# CAN.net
KiCad netlist of a schematic drawn in Altium Designer
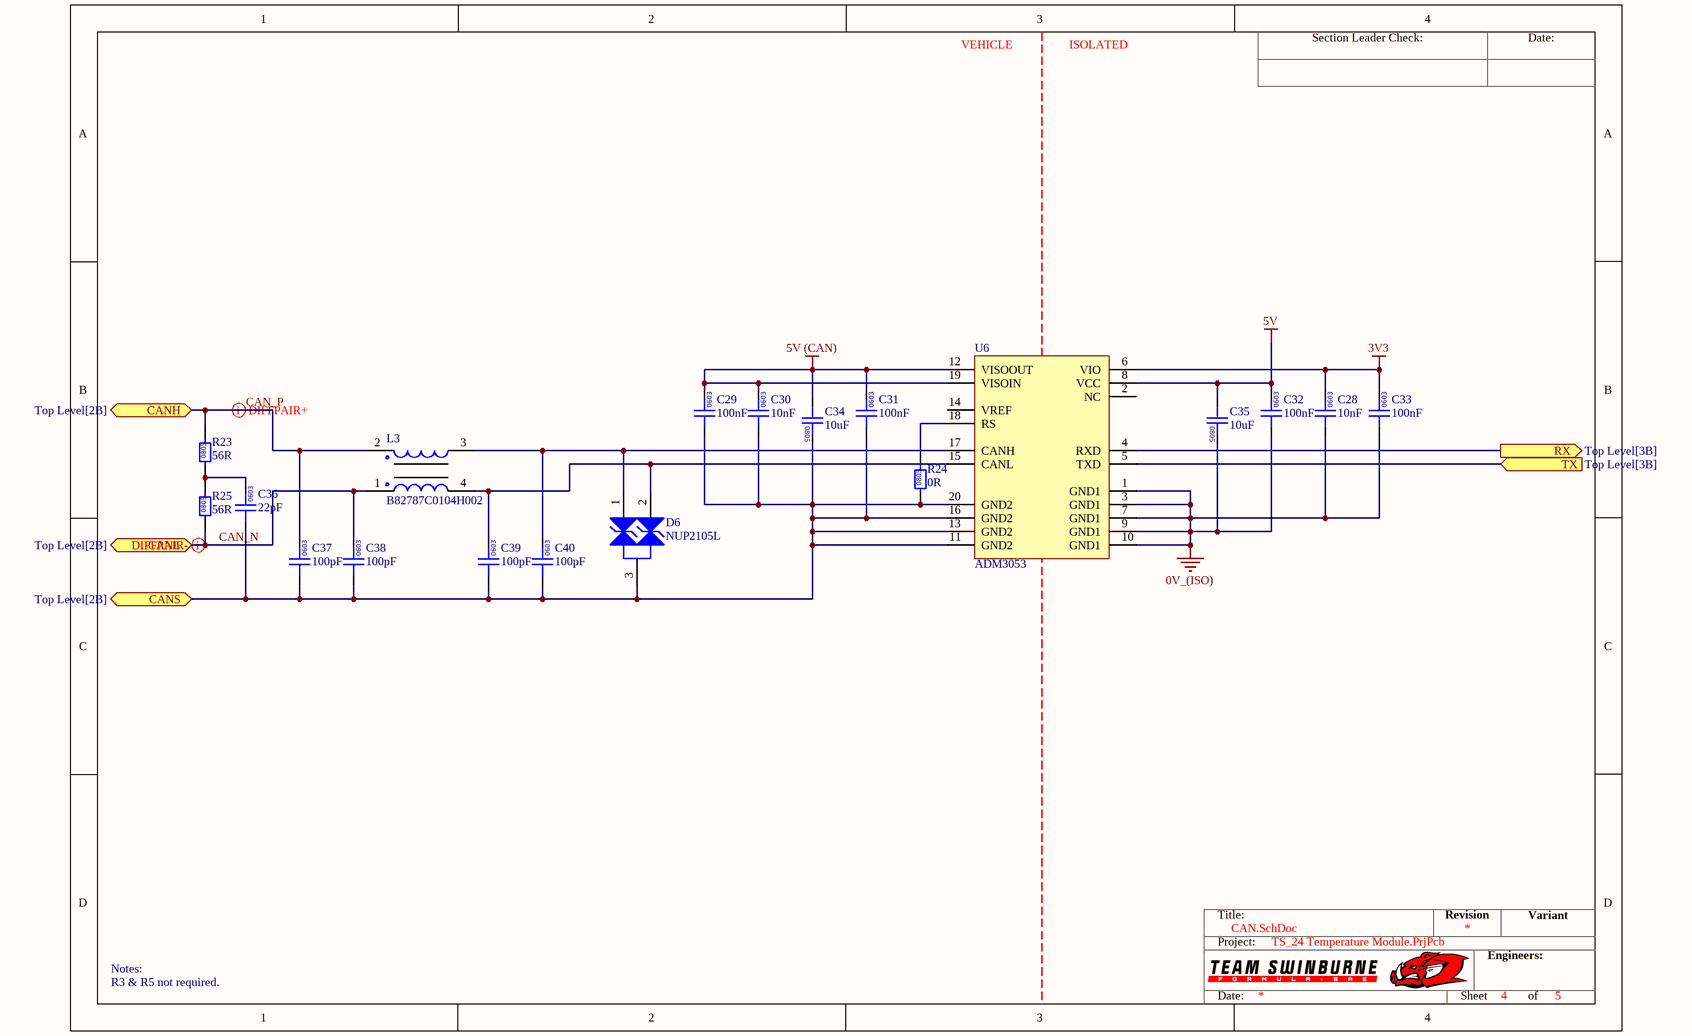
[diagram p0: CAN.SchDoc]

(export (version "E")
  (design (tool "Eeschema 10.0.6"))
  (components
    (comp (ref "C28")
      (value "10nF")
      (footprint "0603")
      (fields
        (field (name "PART NUMBER") "GCM188L81H103KA03D")
        (field (name "MANUFACTURER") "muRata")
        (field (name "TOLERANCE") "±10%")
      )
      (libsource (lib "ts_standard_library") (part "Capacitor 0603"))
    )
    (comp (ref "C29")
      (value "100nF")
      (footprint "0603")
      (fields
        (field (name "PART NUMBER") "GCM188L81H104KA57D")
        (field (name "MANUFACTURER") "muRata")
        (field (name "TOLERANCE") "±10%")
      )
      (libsource (lib "ts_standard_library") (part "Capacitor 0603"))
    )
    (comp (ref "C30")
      (value "10nF")
      (footprint "0603")
      (fields
        (field (name "PART NUMBER") "GCM188L81H103KA03D")
        (field (name "MANUFACTURER") "muRata")
        (field (name "TOLERANCE") "±10%")
      )
      (libsource (lib "ts_standard_library") (part "Capacitor 0603"))
    )
    (comp (ref "C31")
      (value "100nF")
      (footprint "0603")
      (fields
        (field (name "PART NUMBER") "GCM188L81H104KA57D")
        (field (name "MANUFACTURER") "muRata")
        (field (name "TOLERANCE") "±10%")
      )
      (libsource (lib "ts_standard_library") (part "Capacitor 0603"))
    )
    (comp (ref "C32")
      (value "100nF")
      (footprint "0603")
      (fields
        (field (name "PART NUMBER") "GCM188L81H104KA57D")
        (field (name "MANUFACTURER") "muRata")
        (field (name "TOLERANCE") "±10%")
      )
      (libsource (lib "ts_standard_library") (part "Capacitor 0603"))
    )
    (comp (ref "C33")
      (value "100nF")
      (footprint "0603")
      (fields
        (field (name "PART NUMBER") "GCM188L81H104KA57D")
        (field (name "MANUFACTURER") "muRata")
        (field (name "TOLERANCE") "±10%")
      )
      (libsource (lib "ts_standard_library") (part "Capacitor 0603"))
    )
    (comp (ref "C34")
      (value "10uF")
      (footprint "0805")
      (fields
        (field (name "PART NUMBER") "GRM21BR6YA106KE43L")
        (field (name "MANUFACTURER") "muRata")
        (field (name "TOLERANCE") "10%")
      )
      (libsource (lib "ts_standard_library") (part "Capacitor 0805"))
    )
    (comp (ref "C35")
      (value "10uF")
      (footprint "0805")
      (fields
        (field (name "PART NUMBER") "GRM21BR6YA106KE43L")
        (field (name "MANUFACTURER") "muRata")
        (field (name "TOLERANCE") "10%")
      )
      (libsource (lib "ts_standard_library") (part "Capacitor 0805"))
    )
    (comp (ref "C36")
      (value "22pF")
      (footprint "0603")
      (fields
        (field (name "PART NUMBER") "GRM0335C1H220JA01D")
        (field (name "MANUFACTURER") "Murata Electronics")
        (field (name "TOLERANCE") "±5%")
      )
      (libsource (lib "ts_standard_library") (part "Capacitor 0603"))
    )
    (comp (ref "C37")
      (value "100pF")
      (footprint "0603")
      (fields
        (field (name "PART NUMBER") "GRM1885C1H101JA01D")
        (field (name "MANUFACTURER") "Murata Electronics")
        (field (name "TOLERANCE") "±5%")
      )
      (libsource (lib "ts_standard_library") (part "Capacitor 0603"))
    )
    (comp (ref "C38")
      (value "100pF")
      (footprint "0603")
      (fields
        (field (name "PART NUMBER") "GRM1885C1H101JA01D")
        (field (name "MANUFACTURER") "Murata Electronics")
        (field (name "TOLERANCE") "±5%")
      )
      (libsource (lib "ts_standard_library") (part "Capacitor 0603"))
    )
    (comp (ref "C39")
      (value "100pF")
      (footprint "0603")
      (fields
        (field (name "PART NUMBER") "GRM1885C1H101JA01D")
        (field (name "MANUFACTURER") "Murata Electronics")
        (field (name "TOLERANCE") "±5%")
      )
      (libsource (lib "ts_standard_library") (part "Capacitor 0603"))
    )
    (comp (ref "C40")
      (value "100pF")
      (footprint "0603")
      (fields
        (field (name "PART NUMBER") "GRM1885C1H101JA01D")
        (field (name "MANUFACTURER") "Murata Electronics")
        (field (name "TOLERANCE") "±5%")
      )
      (libsource (lib "ts_standard_library") (part "Capacitor 0603"))
    )
    (comp (ref "D6")
      (value "NUP2105L")
      (footprint "ONSC-SOT-23-3-318-08_V")
      (description "NUP2105L Series 350 W Dual Line CAN Bus Protector ESD Protection Diode - SOT-23")
      (libsource (lib "Team Swinburne") (part "ONSC-NUP21X5X-SOT-23-3-318-08"))
    )
    (comp (ref "L3")
      (value "B82787C0104H002")
      (footprint "TDK 4-PC Pad")
      (fields
        (field (name "MANUFACTURER") "EPCOS (TDK)")
        (field (name "DIGIKEY PART NUMBER") "495-4598-1-ND")
      )
      (libsource (lib "ts_standard_library") (part "B82787C0104H002"))
    )
    (comp (ref "R23")
      (value "56R")
      (footprint "0805")
      (fields
        (field (name "PART NUMBER") "RC0805FR0756RL")
        (field (name "MANUFACTURER") "YAGEO")
        (field (name "TOLERANCE") "0.01")
      )
      (libsource (lib "ts_standard_library") (part "Resistor 0805"))
    )
    (comp (ref "R24")
      (value "0R")
      (footprint "0805")
      (fields
        (field (name "PART NUMBER") "RC0805FR070RL")
        (field (name "MANUFACTURER") "YAGEO")
        (field (name "TOLERANCE") "0.01")
      )
      (libsource (lib "ts_standard_library") (part "Resistor 0805"))
    )
    (comp (ref "R25")
      (value "56R")
      (footprint "0805")
      (fields
        (field (name "PART NUMBER") "RC0805FR0756RL")
        (field (name "MANUFACTURER") "YAGEO")
        (field (name "TOLERANCE") "0.01")
      )
      (libsource (lib "ts_standard_library") (part "Resistor 0805"))
    )
    (comp (ref "U6")
      (value "ADM3053")
      (footprint "AD SOIC-W 20")
      (description "Isolated CAN Transceiver")
      (fields
        (field (name "MANUFACTURER") "Analogue Devices")
        (field (name "DIGIKEY PART NUMBER") "ADM3053BRWZ-ND")
      )
      (libsource (lib "ts_standard_library") (part "ADM3053"))
    )
  )
  (nets
    (net (code "1") (name "/CANS") (class "Default")
      (node (ref "C29") (pin "1") (pinfunction "1_1") (pintype "passive"))
      (node (ref "C30") (pin "1") (pinfunction "1_1") (pintype "passive"))
      (node (ref "C31") (pin "1") (pinfunction "1_1") (pintype "passive"))
      (node (ref "C34") (pin "2") (pinfunction "2_2") (pintype "passive"))
      (node (ref "C36") (pin "1") (pinfunction "1_1") (pintype "passive"))
      (node (ref "C37") (pin "1") (pinfunction "1_1") (pintype "passive"))
      (node (ref "C38") (pin "1") (pinfunction "1_1") (pintype "passive"))
      (node (ref "C39") (pin "1") (pinfunction "1_1") (pintype "passive"))
      (node (ref "C40") (pin "1") (pinfunction "1_1") (pintype "passive"))
      (node (ref "D6") (pin "3") (pinfunction "K_3") (pintype "passive"))
      (node (ref "R24") (pin "1") (pinfunction "1_1") (pintype "passive"))
      (node (ref "U6") (pin "11") (pinfunction "GND2_11") (pintype "passive"))
      (node (ref "U6") (pin "13") (pinfunction "GND2_13") (pintype "passive"))
      (node (ref "U6") (pin "16") (pinfunction "GND2_16") (pintype "passive"))
      (node (ref "U6") (pin "20") (pinfunction "GND2_20") (pintype "passive"))
    )
    (net (code "2") (name "/CAN_N") (class "Default")
      (node (ref "C38") (pin "2") (pinfunction "2_2") (pintype "passive"))
      (node (ref "L3") (pin "1") (pinfunction "1_1") (pintype "passive"))
      (node (ref "R25") (pin "1") (pinfunction "1_1") (pintype "passive"))
    )
    (net (code "3") (name "/CAN_P") (class "Default")
      (node (ref "C37") (pin "2") (pinfunction "2_2") (pintype "passive"))
      (node (ref "L3") (pin "2") (pinfunction "2_2") (pintype "passive"))
      (node (ref "R23") (pin "2") (pinfunction "2_2") (pintype "passive"))
    )
    (net (code "4") (name "/RX") (class "Default")
      (node (ref "U6") (pin "4") (pinfunction "RXD_4") (pintype "passive"))
    )
    (net (code "5") (name "/TX") (class "Default")
      (node (ref "U6") (pin "5") (pinfunction "TXD_5") (pintype "passive"))
    )
    (net (code "6") (name "0V_(ISO)") (class "Default")
      (node (ref "C28") (pin "1") (pinfunction "1_1") (pintype "passive"))
      (node (ref "C32") (pin "1") (pinfunction "1_1") (pintype "passive"))
      (node (ref "C33") (pin "1") (pinfunction "1_1") (pintype "passive"))
      (node (ref "C35") (pin "2") (pinfunction "2_2") (pintype "passive"))
      (node (ref "U6") (pin "1") (pinfunction "GND1_1") (pintype "passive"))
      (node (ref "U6") (pin "10") (pinfunction "GND1_10") (pintype "passive"))
      (node (ref "U6") (pin "3") (pinfunction "GND1_3") (pintype "passive"))
      (node (ref "U6") (pin "7") (pinfunction "GND1_7") (pintype "passive"))
      (node (ref "U6") (pin "9") (pinfunction "GND1_9") (pintype "passive"))
    )
    (net (code "7") (name "3V3") (class "Default")
      (node (ref "C28") (pin "2") (pinfunction "2_2") (pintype "passive"))
      (node (ref "C33") (pin "2") (pinfunction "2_2") (pintype "passive"))
      (node (ref "U6") (pin "6") (pinfunction "VIO_6") (pintype "passive"))
    )
    (net (code "8") (name "5V") (class "Default")
      (node (ref "C32") (pin "2") (pinfunction "2_2") (pintype "passive"))
      (node (ref "C35") (pin "1") (pinfunction "1_1") (pintype "passive"))
      (node (ref "U6") (pin "8") (pinfunction "VCC_8") (pintype "passive"))
    )
    (net (code "9") (name "5V (CAN)") (class "Default")
      (node (ref "C29") (pin "2") (pinfunction "2_2") (pintype "passive"))
      (node (ref "C30") (pin "2") (pinfunction "2_2") (pintype "passive"))
      (node (ref "C31") (pin "2") (pinfunction "2_2") (pintype "passive"))
      (node (ref "C34") (pin "1") (pinfunction "1_1") (pintype "passive"))
      (node (ref "U6") (pin "12") (pinfunction "VISOOUT_12") (pintype "passive"))
      (node (ref "U6") (pin "19") (pinfunction "VISOIN_19") (pintype "passive"))
    )
    (net (code "10") (name "Net-(C36-Pad2)") (class "Default")
      (node (ref "C36") (pin "2") (pinfunction "2_2") (pintype "passive"))
      (node (ref "R23") (pin "1") (pinfunction "1_1") (pintype "passive"))
      (node (ref "R25") (pin "2") (pinfunction "2_2") (pintype "passive"))
    )
    (net (code "11") (name "Net-(U6-CANH)") (class "Default")
      (node (ref "C40") (pin "2") (pinfunction "2_2") (pintype "passive"))
      (node (ref "D6") (pin "1") (pinfunction "K_1") (pintype "passive"))
      (node (ref "L3") (pin "3") (pinfunction "3_3") (pintype "passive"))
      (node (ref "U6") (pin "17") (pinfunction "CANH_17") (pintype "passive"))
    )
    (net (code "12") (name "Net-(U6-CANL)") (class "Default")
      (node (ref "C39") (pin "2") (pinfunction "2_2") (pintype "passive"))
      (node (ref "D6") (pin "2") (pinfunction "K_2") (pintype "passive"))
      (node (ref "L3") (pin "4") (pinfunction "4_4") (pintype "passive"))
      (node (ref "U6") (pin "15") (pinfunction "CANL_15") (pintype "passive"))
    )
    (net (code "13") (name "Net-(U6-RS)") (class "Default")
      (node (ref "R24") (pin "2") (pinfunction "2_2") (pintype "passive"))
      (node (ref "U6") (pin "18") (pinfunction "RS_18") (pintype "passive"))
    )
    (net (code "14") (name "unconnected-(U6-NC-Pad2)") (class "Default")
      (node (ref "U6") (pin "2") (pinfunction "NC_2") (pintype "passive"))
    )
    (net (code "15") (name "unconnected-(U6-VREF-Pad14)") (class "Default")
      (node (ref "U6") (pin "14") (pinfunction "VREF_14") (pintype "passive"))
    )
  )
)
